# ServoFaderTB6612_V_1_0.net
KiCad netlist of a schematic drawn in EAGLE
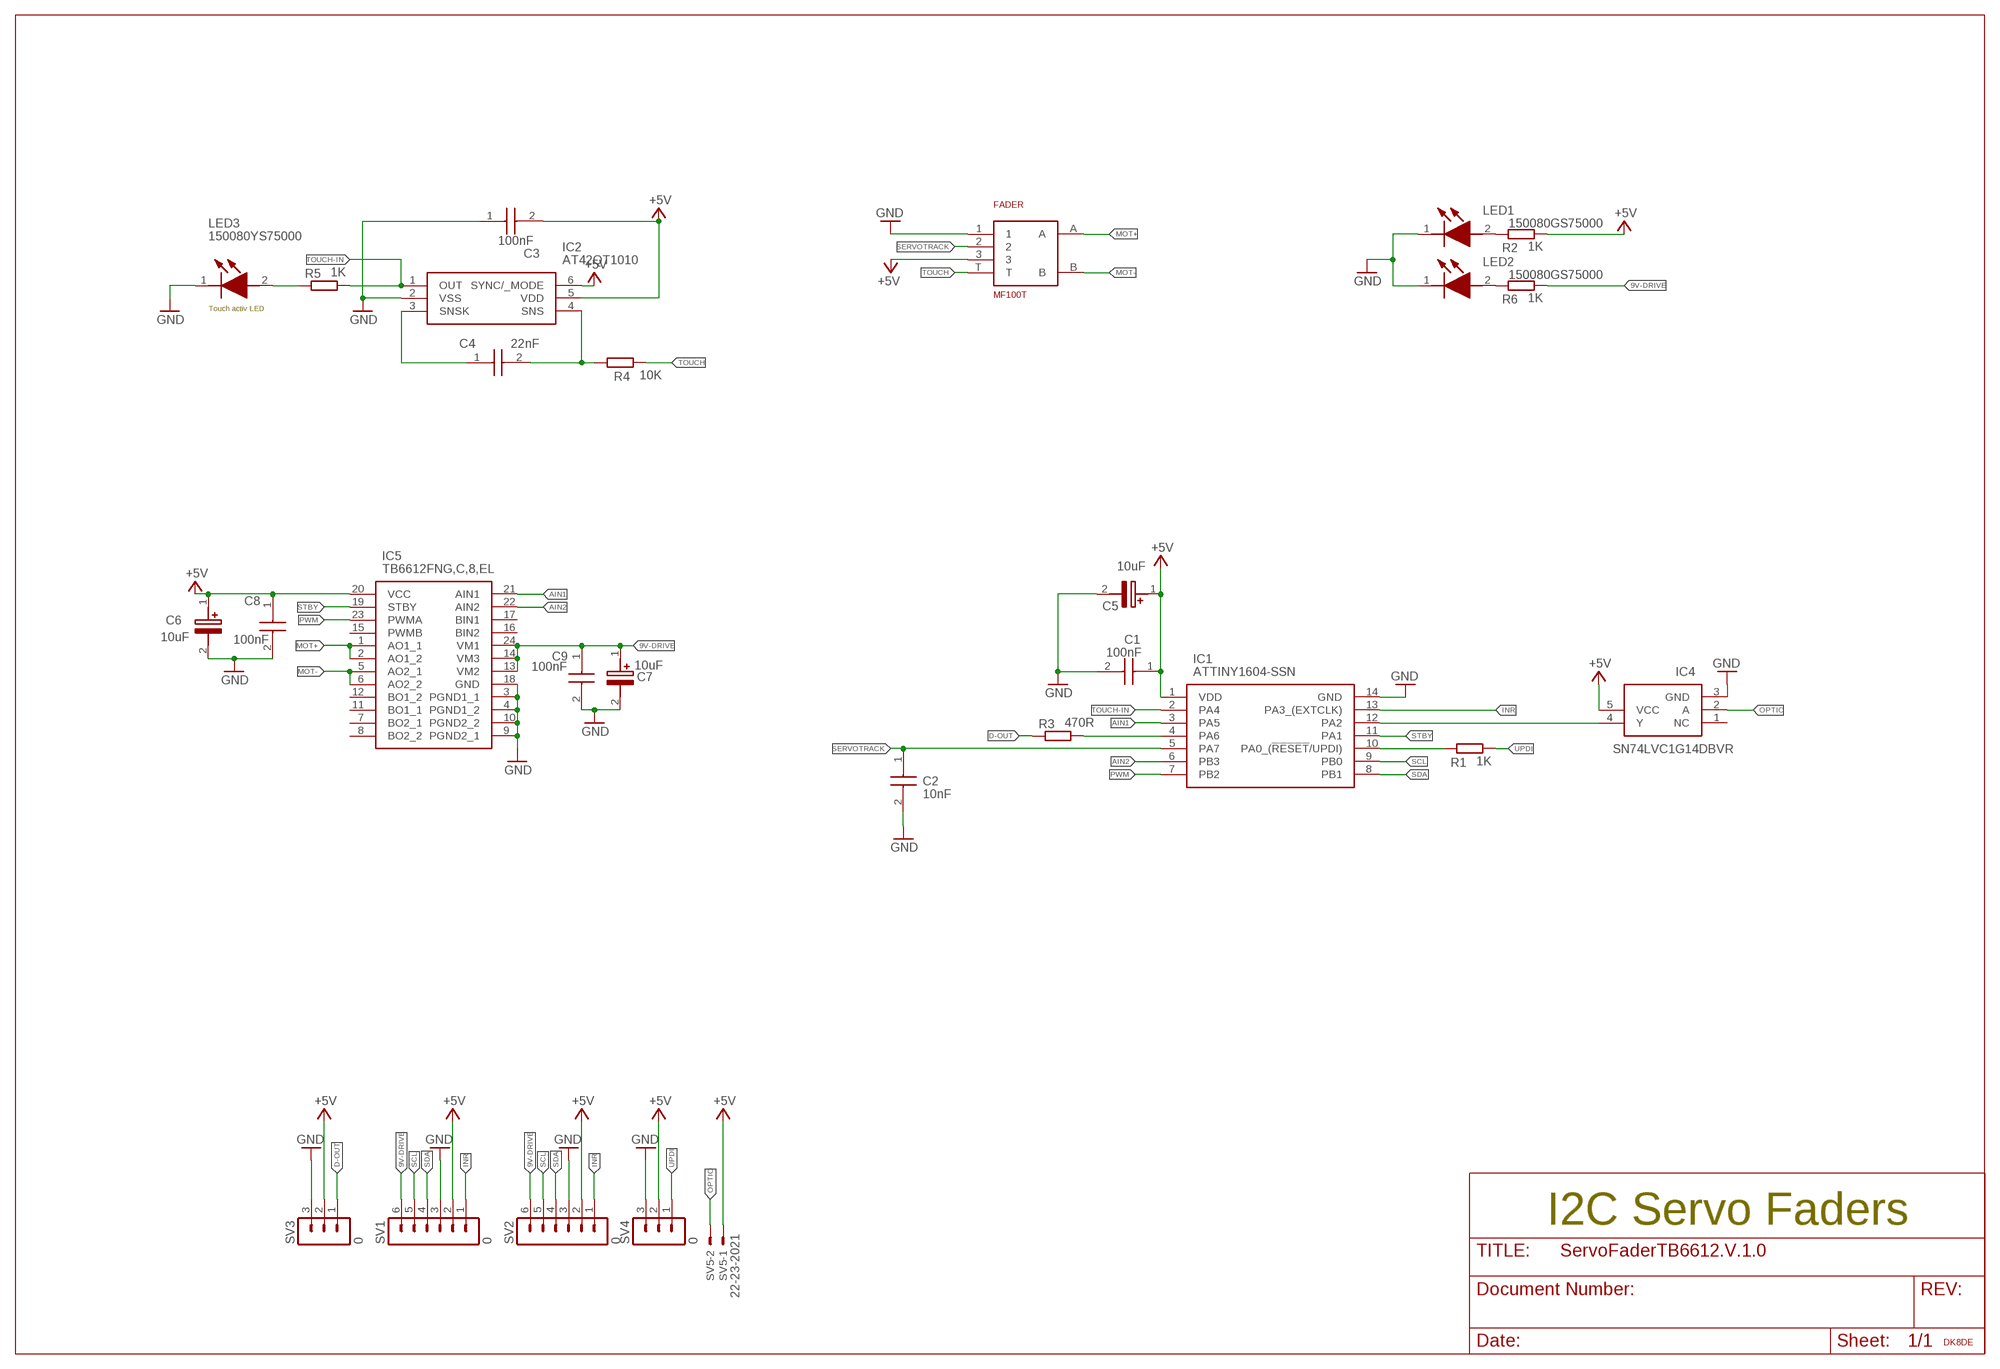
[diagram p0: schematic, sheet 1]

(export (version "E")
  (design (tool "Eeschema 10.0.6"))
  (components
    (comp (ref "C1")
      (value "100nF")
      (footprint "eagle-import:C0805")
      (fields
        (field (name "MANUFACTURER_PART_NUMBER") "C0805C104K1RACTU")
        (field (name "MOUSER_PART_NUMBER") "80-C0805C104K1R")
      )
      (libsource (lib "eagle-import") (part "C0805C104K1RACTU"))
    )
    (comp (ref "C2")
      (value "10nF")
      (footprint "eagle-import:C0805")
      (fields
        (field (name "MANUFACTURER_PART_NUMBER") "C0805Y103K4RACTU")
        (field (name "MOUSER_PART_NUMBER") "80-C0805Y103K4R")
      )
      (libsource (lib "eagle-import") (part "C0805Y103K4RACTU"))
    )
    (comp (ref "C3")
      (value "100nF")
      (footprint "eagle-import:C0805")
      (fields (field (name "MANUFACTURER_PART_NUMBER") "C0805C223K5RAC7210"))
      (libsource (lib "eagle-import") (part "C0805C223K5RAC7210"))
    )
    (comp (ref "C4")
      (value "22nF")
      (footprint "eagle-import:C0805")
      (fields (field (name "MANUFACTURER_PART_NUMBER") "C0805C223K5RAC7210"))
      (libsource (lib "eagle-import") (part "C0805C223K5RAC7210"))
    )
    (comp (ref "C5")
      (value "10uF")
      (footprint "eagle-import:T491A")
      (fields
        (field (name "MANUFACTURER_PART_NUMBER") "T491A106M016AT7280")
        (field (name "MOUSER_PART_NUMBER") "80-T491A106M16AT7280")
      )
      (libsource (lib "eagle-import") (part "T491A106M016AT7280"))
    )
    (comp (ref "C6")
      (value "10uF")
      (footprint "eagle-import:T491A")
      (fields
        (field (name "MANUFACTURER_PART_NUMBER") "T491A106M016AT7280")
        (field (name "MOUSER_PART_NUMBER") "80-T491A106M16AT7280")
      )
      (libsource (lib "eagle-import") (part "T491A106M016AT7280"))
    )
    (comp (ref "C7")
      (value "10uF")
      (footprint "eagle-import:T491A")
      (fields
        (field (name "MANUFACTURER_PART_NUMBER") "T491A106M016AT7280")
        (field (name "MOUSER_PART_NUMBER") "80-T491A106M16AT7280")
      )
      (libsource (lib "eagle-import") (part "T491A106M016AT7280"))
    )
    (comp (ref "C8")
      (value "100nF")
      (footprint "eagle-import:C0805")
      (fields
        (field (name "MANUFACTURER_PART_NUMBER") "C0805C104K1RACTU")
        (field (name "MOUSER_PART_NUMBER") "80-C0805C104K1R")
      )
      (libsource (lib "eagle-import") (part "C0805C104K1RACTU"))
    )
    (comp (ref "C9")
      (value "100nF")
      (footprint "eagle-import:C0805")
      (fields
        (field (name "MANUFACTURER_PART_NUMBER") "C0805C104K1RACTU")
        (field (name "MOUSER_PART_NUMBER") "80-C0805C104K1R")
      )
      (libsource (lib "eagle-import") (part "C0805C104K1RACTU"))
    )
    (comp (ref "FADER")
      (value "MF100T")
      (footprint "eagle-import:SM10001NKA0X-HA1")
      (libsource (lib "eagle-import") (part "SM10001NKA0X-HA1"))
    )
    (comp (ref "IC1")
      (value "ATTINY1604-SSN")
      (footprint "eagle-import:SOIC127P600X175-14N")
      (fields (field (name "MOUSER_PART_NUMBER") "556-ATTINY1604-SSN"))
      (libsource (lib "eagle-import") (part "ATTINY1604-SSN"))
    )
    (comp (ref "IC2")
      (value "AT42QT1010")
      (footprint "eagle-import:SOT95P280X145-6N")
      (fields
        (field (name "MANUFACTURER_PART_NUMBER") "AT42QT1010-TSHR")
        (field (name "MOUSER_PART_NUMBER") "556-AT42QT1010-TSHR")
      )
      (libsource (lib "eagle-import") (part "AT42QT1010-TSHR"))
    )
    (comp (ref "IC4")
      (value "SN74LVC1G14DBVR")
      (footprint "eagle-import:SOT95P280X145-5N")
      (fields (field (name "MOUSER_PART_NUMBER") "595-SN74LVC1G14DBVR"))
      (libsource (lib "eagle-import") (part "SN74LVC1G14DBVR"))
    )
    (comp (ref "IC5")
      (value "TB6612FNG,C,8,EL")
      (footprint "eagle-import:SOP65P760X160-24N")
      (fields (field (name "MOUSER_PART_NUMBER") "757-TB6612FNGC8EL"))
      (libsource (lib "eagle-import") (part "TB6612FNG,C,8,EL"))
    )
    (comp (ref "LED1")
      (value "150080GS75000")
      (footprint "eagle-import:LEDM2012X80N")
      (fields (field (name "MOUSER_PART_NUMBER") "710-150080GS75000"))
      (libsource (lib "eagle-import") (part "150080GS75000"))
    )
    (comp (ref "LED2")
      (value "150080GS75000")
      (footprint "eagle-import:LEDM2012X80N")
      (fields (field (name "MOUSER_PART_NUMBER") "710-150080GS75000"))
      (libsource (lib "eagle-import") (part "150080GS75000"))
    )
    (comp (ref "LED3")
      (value "150080YS75000")
      (footprint "eagle-import:LEDC2012X80N")
      (fields (field (name "MOUSER_PART_NUMBER") "710-150080YS75000"))
      (libsource (lib "eagle-import") (part "150080YS75000"))
    )
    (comp (ref "LOGO")
      (value "DK8DESS")
      (footprint "eagle-import:DK8DE_KLEIN")
      (libsource (lib "eagle-import") (part "DK8DESS"))
    )
    (comp (ref "R1")
      (value "1K")
      (footprint "eagle-import:R0805")
      (libsource (lib "eagle-import") (part "R-EU_R0805"))
    )
    (comp (ref "R2")
      (value "1K")
      (footprint "eagle-import:R0805")
      (libsource (lib "eagle-import") (part "R-EU_R0805"))
    )
    (comp (ref "R3")
      (value "470R")
      (footprint "eagle-import:R0805")
      (libsource (lib "eagle-import") (part "R-EU_R0805"))
    )
    (comp (ref "R4")
      (value "10K")
      (footprint "eagle-import:R0805")
      (libsource (lib "eagle-import") (part "R-EU_R0805"))
    )
    (comp (ref "R5")
      (value "1K")
      (footprint "eagle-import:R0805")
      (libsource (lib "eagle-import") (part "R-EU_R0805"))
    )
    (comp (ref "R6")
      (value "1K")
      (footprint "eagle-import:R0805")
      (libsource (lib "eagle-import") (part "R-EU_R0805"))
    )
    (comp (ref "SV1")
      (value "0")
      (footprint "eagle-import:MA06-1")
      (libsource (lib "eagle-import") (part "MA06-1"))
    )
    (comp (ref "SV2")
      (value "0")
      (footprint "eagle-import:MA06-1")
      (libsource (lib "eagle-import") (part "MA06-1"))
    )
    (comp (ref "SV3")
      (value "0")
      (footprint "eagle-import:MA03-1")
      (libsource (lib "eagle-import") (part "MA03-1"))
    )
    (comp (ref "SV4")
      (value "0")
      (footprint "eagle-import:MA03-1")
      (libsource (lib "eagle-import") (part "MA03-1"))
    )
    (comp (ref "SV5")
      (value "22-23-2021")
      (footprint "eagle-import:22-23-2021")
      (fields (field (name "MF") "MOLEX"))
      (libsource (lib "eagle-import") (part "22-23-2021"))
    )
  )
  (nets
    (net (code "1") (name "+5V") (class "Default")
      (node (ref "C1") (pin "1") (pinfunction "1_1") (pintype "bidirectional"))
      (node (ref "C3") (pin "2") (pinfunction "2_2") (pintype "bidirectional"))
      (node (ref "C5") (pin "1") (pinfunction "+_1") (pintype "bidirectional"))
      (node (ref "C6") (pin "1") (pinfunction "+_1") (pintype "bidirectional"))
      (node (ref "C8") (pin "1") (pinfunction "1_1") (pintype "bidirectional"))
      (node (ref "FADER") (pin "3") (pinfunction "3_3") (pintype "bidirectional"))
      (node (ref "IC1") (pin "1") (pinfunction "VDD_1") (pintype "bidirectional"))
      (node (ref "IC2") (pin "5") (pinfunction "VDD_5") (pintype "bidirectional"))
      (node (ref "IC2") (pin "6") (pinfunction "SYNC/_MODE_6") (pintype "bidirectional"))
      (node (ref "IC4") (pin "5") (pinfunction "VCC_5") (pintype "bidirectional"))
      (node (ref "IC5") (pin "20") (pinfunction "VCC_20") (pintype "bidirectional"))
      (node (ref "R2") (pin "2") (pinfunction "2_2") (pintype "passive"))
      (node (ref "SV1") (pin "2") (pinfunction "2_2") (pintype "passive"))
      (node (ref "SV2") (pin "2") (pinfunction "2_2") (pintype "passive"))
      (node (ref "SV3") (pin "2") (pinfunction "2_2") (pintype "passive"))
      (node (ref "SV4") (pin "2") (pinfunction "2_2") (pintype "passive"))
      (node (ref "SV5") (pin "1") (pinfunction "S_1") (pintype "passive"))
    )
    (net (code "2") (name "9V-DRIVE") (class "Default")
      (node (ref "C7") (pin "1") (pinfunction "+_1") (pintype "bidirectional"))
      (node (ref "C9") (pin "1") (pinfunction "1_1") (pintype "bidirectional"))
      (node (ref "IC5") (pin "13") (pinfunction "VM2_13") (pintype "bidirectional"))
      (node (ref "IC5") (pin "14") (pinfunction "VM3_14") (pintype "bidirectional"))
      (node (ref "IC5") (pin "24") (pinfunction "VM1_24") (pintype "bidirectional"))
      (node (ref "R6") (pin "2") (pinfunction "2_2") (pintype "passive"))
      (node (ref "SV1") (pin "6") (pinfunction "6_6") (pintype "passive"))
      (node (ref "SV2") (pin "6") (pinfunction "6_6") (pintype "passive"))
    )
    (net (code "3") (name "AIN1") (class "Default")
      (node (ref "IC1") (pin "3") (pinfunction "PA5_3") (pintype "bidirectional"))
      (node (ref "IC5") (pin "21") (pinfunction "AIN1_21") (pintype "bidirectional"))
    )
    (net (code "4") (name "AIN2") (class "Default")
      (node (ref "IC1") (pin "6") (pinfunction "PB3_6") (pintype "bidirectional"))
      (node (ref "IC5") (pin "22") (pinfunction "AIN2_22") (pintype "bidirectional"))
    )
    (net (code "5") (name "D-OUT") (class "Default")
      (node (ref "R3") (pin "1") (pinfunction "1_1") (pintype "passive"))
      (node (ref "SV3") (pin "1") (pinfunction "1_1") (pintype "passive"))
    )
    (net (code "6") (name "GND") (class "Default")
      (node (ref "C1") (pin "2") (pinfunction "2_2") (pintype "bidirectional"))
      (node (ref "C2") (pin "2") (pinfunction "2_2") (pintype "bidirectional"))
      (node (ref "C3") (pin "1") (pinfunction "1_1") (pintype "bidirectional"))
      (node (ref "C5") (pin "2") (pinfunction "-_2") (pintype "bidirectional"))
      (node (ref "C6") (pin "2") (pinfunction "-_2") (pintype "bidirectional"))
      (node (ref "C7") (pin "2") (pinfunction "-_2") (pintype "bidirectional"))
      (node (ref "C8") (pin "2") (pinfunction "2_2") (pintype "bidirectional"))
      (node (ref "C9") (pin "2") (pinfunction "2_2") (pintype "bidirectional"))
      (node (ref "FADER") (pin "1") (pinfunction "1_1") (pintype "bidirectional"))
      (node (ref "IC1") (pin "14") (pinfunction "GND_14") (pintype "bidirectional"))
      (node (ref "IC2") (pin "2") (pinfunction "VSS_2") (pintype "bidirectional"))
      (node (ref "IC4") (pin "3") (pinfunction "GND_3") (pintype "bidirectional"))
      (node (ref "IC5") (pin "10") (pinfunction "PGND2_2_10") (pintype "bidirectional"))
      (node (ref "IC5") (pin "18") (pinfunction "GND_18") (pintype "bidirectional"))
      (node (ref "IC5") (pin "3") (pinfunction "PGND1_1_3") (pintype "bidirectional"))
      (node (ref "IC5") (pin "4") (pinfunction "PGND1_2_4") (pintype "bidirectional"))
      (node (ref "IC5") (pin "9") (pinfunction "PGND2_1_9") (pintype "bidirectional"))
      (node (ref "LED1") (pin "1") (pinfunction "K_1") (pintype "bidirectional"))
      (node (ref "LED2") (pin "1") (pinfunction "K_1") (pintype "bidirectional"))
      (node (ref "LED3") (pin "1") (pinfunction "K_1") (pintype "bidirectional"))
      (node (ref "SV1") (pin "3") (pinfunction "3_3") (pintype "passive"))
      (node (ref "SV2") (pin "3") (pinfunction "3_3") (pintype "passive"))
      (node (ref "SV3") (pin "3") (pinfunction "3_3") (pintype "passive"))
      (node (ref "SV4") (pin "3") (pinfunction "3_3") (pintype "passive"))
    )
    (net (code "7") (name "INR") (class "Default")
      (node (ref "IC1") (pin "13") (pinfunction "PA3_(EXTCLK)_13") (pintype "bidirectional"))
      (node (ref "SV1") (pin "1") (pinfunction "1_1") (pintype "passive"))
      (node (ref "SV2") (pin "1") (pinfunction "1_1") (pintype "passive"))
    )
    (net (code "8") (name "MOT+") (class "Default")
      (node (ref "FADER") (pin "A") (pinfunction "A_A") (pintype "bidirectional"))
      (node (ref "IC5") (pin "1") (pinfunction "AO1_1_1") (pintype "bidirectional"))
      (node (ref "IC5") (pin "2") (pinfunction "AO1_2_2") (pintype "bidirectional"))
    )
    (net (code "9") (name "MOT-") (class "Default")
      (node (ref "FADER") (pin "B") (pinfunction "B_B") (pintype "bidirectional"))
      (node (ref "IC5") (pin "5") (pinfunction "AO2_1_5") (pintype "bidirectional"))
      (node (ref "IC5") (pin "6") (pinfunction "AO2_2_6") (pintype "bidirectional"))
    )
    (net (code "10") (name "Net-(IC1-PA0_(~{RESET}{slash}UPDI))") (class "Default")
      (node (ref "IC1") (pin "10") (pinfunction "PA0_(~{RESET}/UPDI)_10") (pintype "bidirectional"))
      (node (ref "R1") (pin "1") (pinfunction "1_1") (pintype "passive"))
    )
    (net (code "11") (name "Net-(IC1-PA2)") (class "Default")
      (node (ref "IC1") (pin "12") (pinfunction "PA2_12") (pintype "bidirectional"))
      (node (ref "IC4") (pin "4") (pinfunction "Y_4") (pintype "bidirectional"))
    )
    (net (code "12") (name "Net-(IC1-PA6)") (class "Default")
      (node (ref "IC1") (pin "4") (pinfunction "PA6_4") (pintype "bidirectional"))
      (node (ref "R3") (pin "2") (pinfunction "2_2") (pintype "passive"))
    )
    (net (code "13") (name "Net-(IC2-SNS)") (class "Default")
      (node (ref "C4") (pin "2") (pinfunction "2_2") (pintype "bidirectional"))
      (node (ref "IC2") (pin "4") (pinfunction "SNS_4") (pintype "bidirectional"))
      (node (ref "R4") (pin "1") (pinfunction "1_1") (pintype "passive"))
    )
    (net (code "14") (name "Net-(IC2-SNSK)") (class "Default")
      (node (ref "C4") (pin "1") (pinfunction "1_1") (pintype "bidirectional"))
      (node (ref "IC2") (pin "3") (pinfunction "SNSK_3") (pintype "bidirectional"))
    )
    (net (code "15") (name "Net-(LED1-A)") (class "Default")
      (node (ref "LED1") (pin "2") (pinfunction "A_2") (pintype "bidirectional"))
      (node (ref "R2") (pin "1") (pinfunction "1_1") (pintype "passive"))
    )
    (net (code "16") (name "Net-(LED2-A)") (class "Default")
      (node (ref "LED2") (pin "2") (pinfunction "A_2") (pintype "bidirectional"))
      (node (ref "R6") (pin "1") (pinfunction "1_1") (pintype "passive"))
    )
    (net (code "17") (name "Net-(LED3-A)") (class "Default")
      (node (ref "LED3") (pin "2") (pinfunction "A_2") (pintype "bidirectional"))
      (node (ref "R5") (pin "1") (pinfunction "1_1") (pintype "passive"))
    )
    (net (code "18") (name "OPTIO") (class "Default")
      (node (ref "IC4") (pin "2") (pinfunction "A_2") (pintype "bidirectional"))
      (node (ref "SV5") (pin "2") (pinfunction "S_2") (pintype "passive"))
    )
    (net (code "19") (name "PWM") (class "Default")
      (node (ref "IC1") (pin "7") (pinfunction "PB2_7") (pintype "bidirectional"))
      (node (ref "IC5") (pin "23") (pinfunction "PWMA_23") (pintype "bidirectional"))
    )
    (net (code "20") (name "SCL") (class "Default")
      (node (ref "IC1") (pin "9") (pinfunction "PB0_9") (pintype "bidirectional"))
      (node (ref "SV1") (pin "5") (pinfunction "5_5") (pintype "passive"))
      (node (ref "SV2") (pin "5") (pinfunction "5_5") (pintype "passive"))
    )
    (net (code "21") (name "SDA") (class "Default")
      (node (ref "IC1") (pin "8") (pinfunction "PB1_8") (pintype "bidirectional"))
      (node (ref "SV1") (pin "4") (pinfunction "4_4") (pintype "passive"))
      (node (ref "SV2") (pin "4") (pinfunction "4_4") (pintype "passive"))
    )
    (net (code "22") (name "SERVOTRACK") (class "Default")
      (node (ref "C2") (pin "1") (pinfunction "1_1") (pintype "bidirectional"))
      (node (ref "FADER") (pin "2") (pinfunction "2_2") (pintype "bidirectional"))
      (node (ref "IC1") (pin "5") (pinfunction "PA7_5") (pintype "bidirectional"))
    )
    (net (code "23") (name "STBY") (class "Default")
      (node (ref "IC1") (pin "11") (pinfunction "PA1_11") (pintype "bidirectional"))
      (node (ref "IC5") (pin "19") (pinfunction "STBY_19") (pintype "bidirectional"))
    )
    (net (code "24") (name "TOUCH") (class "Default")
      (node (ref "FADER") (pin "T") (pinfunction "T_T") (pintype "bidirectional"))
      (node (ref "R4") (pin "2") (pinfunction "2_2") (pintype "passive"))
    )
    (net (code "25") (name "TOUCH-IN") (class "Default")
      (node (ref "IC1") (pin "2") (pinfunction "PA4_2") (pintype "bidirectional"))
      (node (ref "IC2") (pin "1") (pinfunction "OUT_1") (pintype "bidirectional"))
      (node (ref "R5") (pin "2") (pinfunction "2_2") (pintype "passive"))
    )
    (net (code "26") (name "UPDI") (class "Default")
      (node (ref "R1") (pin "2") (pinfunction "2_2") (pintype "passive"))
      (node (ref "SV4") (pin "1") (pinfunction "1_1") (pintype "passive"))
    )
    (net (code "27") (name "unconnected-(IC4-NC-Pad1)") (class "Default")
      (node (ref "IC4") (pin "1") (pinfunction "NC_1") (pintype "no_connect"))
    )
    (net (code "28") (name "unconnected-(IC5-BIN1-Pad17)") (class "Default")
      (node (ref "IC5") (pin "17") (pinfunction "BIN1_17") (pintype "bidirectional"))
    )
    (net (code "29") (name "unconnected-(IC5-BIN2-Pad16)") (class "Default")
      (node (ref "IC5") (pin "16") (pinfunction "BIN2_16") (pintype "bidirectional"))
    )
    (net (code "30") (name "unconnected-(IC5-BO1_1-Pad11)") (class "Default")
      (node (ref "IC5") (pin "11") (pinfunction "BO1_1_11") (pintype "bidirectional"))
    )
    (net (code "31") (name "unconnected-(IC5-BO1_2-Pad12)") (class "Default")
      (node (ref "IC5") (pin "12") (pinfunction "BO1_2_12") (pintype "bidirectional"))
    )
    (net (code "32") (name "unconnected-(IC5-BO2_1-Pad7)") (class "Default")
      (node (ref "IC5") (pin "7") (pinfunction "BO2_1_7") (pintype "bidirectional"))
    )
    (net (code "33") (name "unconnected-(IC5-BO2_2-Pad8)") (class "Default")
      (node (ref "IC5") (pin "8") (pinfunction "BO2_2_8") (pintype "bidirectional"))
    )
    (net (code "34") (name "unconnected-(IC5-PWMB-Pad15)") (class "Default")
      (node (ref "IC5") (pin "15") (pinfunction "PWMB_15") (pintype "bidirectional"))
    )
  )
)
